# offset.net
KiCad netlist of a schematic drawn in Altium Designer
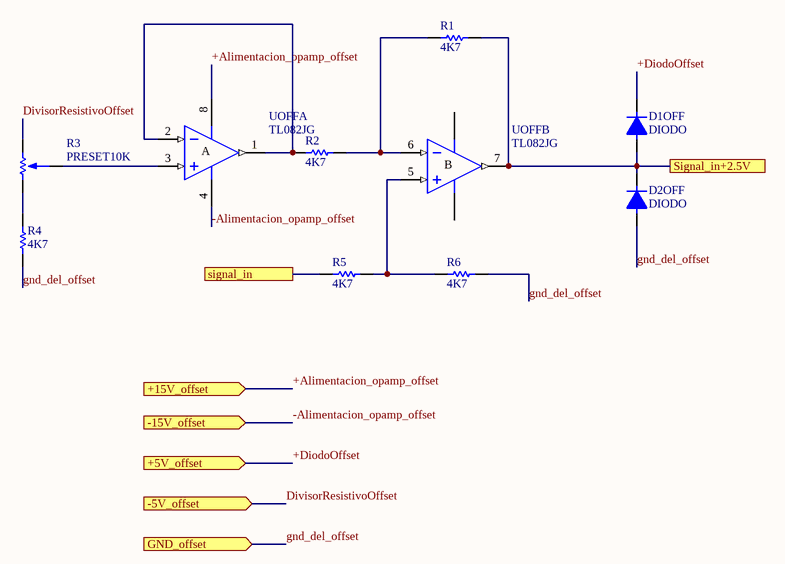
[diagram p0: offset.SchDoc]

(export (version "E")
  (design (tool "Eeschema 10.0.6"))
  (components
    (comp (ref "D1OFF") (value "DIODO") (footprint "DO41") (libsource (lib "LIBEBAL") (part "DIODO")))
    (comp (ref "D2OFF") (value "DIODO") (footprint "DO41") (libsource (lib "LIBEBAL") (part "DIODO")))
    (comp (ref "R1") (value "4K7") (footprint "RES400") (libsource (lib "LIBEBAL") (part "RES")))
    (comp (ref "R2") (value "4K7") (footprint "RES400") (libsource (lib "LIBEBAL") (part "RES")))
    (comp (ref "R3") (value "PRESET10K") (footprint "PRESET V") (libsource (lib "LIBEBAL") (part "PRESET")))
    (comp (ref "R4") (value "4K7") (footprint "RES400") (libsource (lib "LIBEBAL") (part "RES")))
    (comp (ref "R5") (value "4K7") (footprint "RES400") (libsource (lib "LIBEBAL") (part "RES")))
    (comp (ref "R6") (value "4K7") (footprint "RES400") (libsource (lib "LIBEBAL") (part "RES")))
    (comp (ref "UOFF")
      (value "TL082JG")
      (footprint "JG008")
      (description "JFET-Input Operational Amplifier")
      (fields (field (name "PUBLISHER") "Altium Limited"))
      (libsource (lib "TI Operational Amplifier") (part "TL082JG"))
    )
  )
  (nets
    (net (code "1") (name "/+Alimentacion_opamp_offset") (class "Default")
      (node (ref "UOFF") (pin "8") (pinfunction "V+_8") (pintype "power_in"))
    )
    (net (code "2") (name "/+DiodoOffset") (class "Default")
      (node (ref "D1OFF") (pin "2") (pinfunction "2_2") (pintype "passive"))
    )
    (net (code "3") (name "/-Alimentacion_opamp_offset") (class "Default")
      (node (ref "UOFF") (pin "4") (pinfunction "V-_4") (pintype "power_in"))
    )
    (net (code "4") (name "/DivisorResistivoOffset") (class "Default")
      (node (ref "R3") (pin "1") (pinfunction "1_1") (pintype "passive"))
    )
    (net (code "5") (name "/Signal_in+2.5V") (class "Default")
      (node (ref "D1OFF") (pin "1") (pinfunction "1_1") (pintype "passive"))
      (node (ref "D2OFF") (pin "2") (pinfunction "2_2") (pintype "passive"))
      (node (ref "R1") (pin "1") (pinfunction "1_1") (pintype "passive"))
      (node (ref "UOFF") (pin "7") (pinfunction "OUT_7") (pintype "output"))
    )
    (net (code "6") (name "/gnd_del_offset") (class "Default")
      (node (ref "D2OFF") (pin "1") (pinfunction "1_1") (pintype "passive"))
      (node (ref "R4") (pin "1") (pinfunction "1_1") (pintype "passive"))
      (node (ref "R6") (pin "1") (pinfunction "1_1") (pintype "passive"))
    )
    (net (code "7") (name "/signal_in") (class "Default")
      (node (ref "R5") (pin "2") (pinfunction "2_2") (pintype "passive"))
    )
    (net (code "8") (name "Net-(R3-Pad3)") (class "Default")
      (node (ref "R3") (pin "3") (pinfunction "3_3") (pintype "passive"))
      (node (ref "R4") (pin "2") (pinfunction "2_2") (pintype "passive"))
    )
    (net (code "9") (name "Net-(UOFFA-IN+)") (class "Default")
      (node (ref "R3") (pin "2") (pinfunction "2_2") (pintype "passive"))
      (node (ref "UOFF") (pin "3") (pinfunction "IN+_3") (pintype "input"))
    )
    (net (code "10") (name "Net-(UOFFA-IN-)") (class "Default")
      (node (ref "R2") (pin "2") (pinfunction "2_2") (pintype "passive"))
      (node (ref "UOFF") (pin "1") (pinfunction "OUT_1") (pintype "output"))
      (node (ref "UOFF") (pin "2") (pinfunction "IN-_2") (pintype "input"))
    )
    (net (code "11") (name "Net-(UOFFB-IN+)") (class "Default")
      (node (ref "R5") (pin "1") (pinfunction "1_1") (pintype "passive"))
      (node (ref "R6") (pin "2") (pinfunction "2_2") (pintype "passive"))
      (node (ref "UOFF") (pin "5") (pinfunction "IN+_5") (pintype "input"))
    )
    (net (code "12") (name "Net-(UOFFB-IN-)") (class "Default")
      (node (ref "R1") (pin "2") (pinfunction "2_2") (pintype "passive"))
      (node (ref "R2") (pin "1") (pinfunction "1_1") (pintype "passive"))
      (node (ref "UOFF") (pin "6") (pinfunction "IN-_6") (pintype "input"))
    )
    (net (code "13") (name "unconnected-(UOFFB-V+-Pad8)") (class "Default")
      (node (ref "UOFF") (pin "8") (pinfunction "V+_8") (pintype "power_in"))
    )
    (net (code "14") (name "unconnected-(UOFFB-V--Pad4)") (class "Default")
      (node (ref "UOFF") (pin "4") (pinfunction "V-_4") (pintype "power_in"))
    )
  )
)
